# Power_Components.net
KiCad netlist of a schematic drawn in Altium Designer
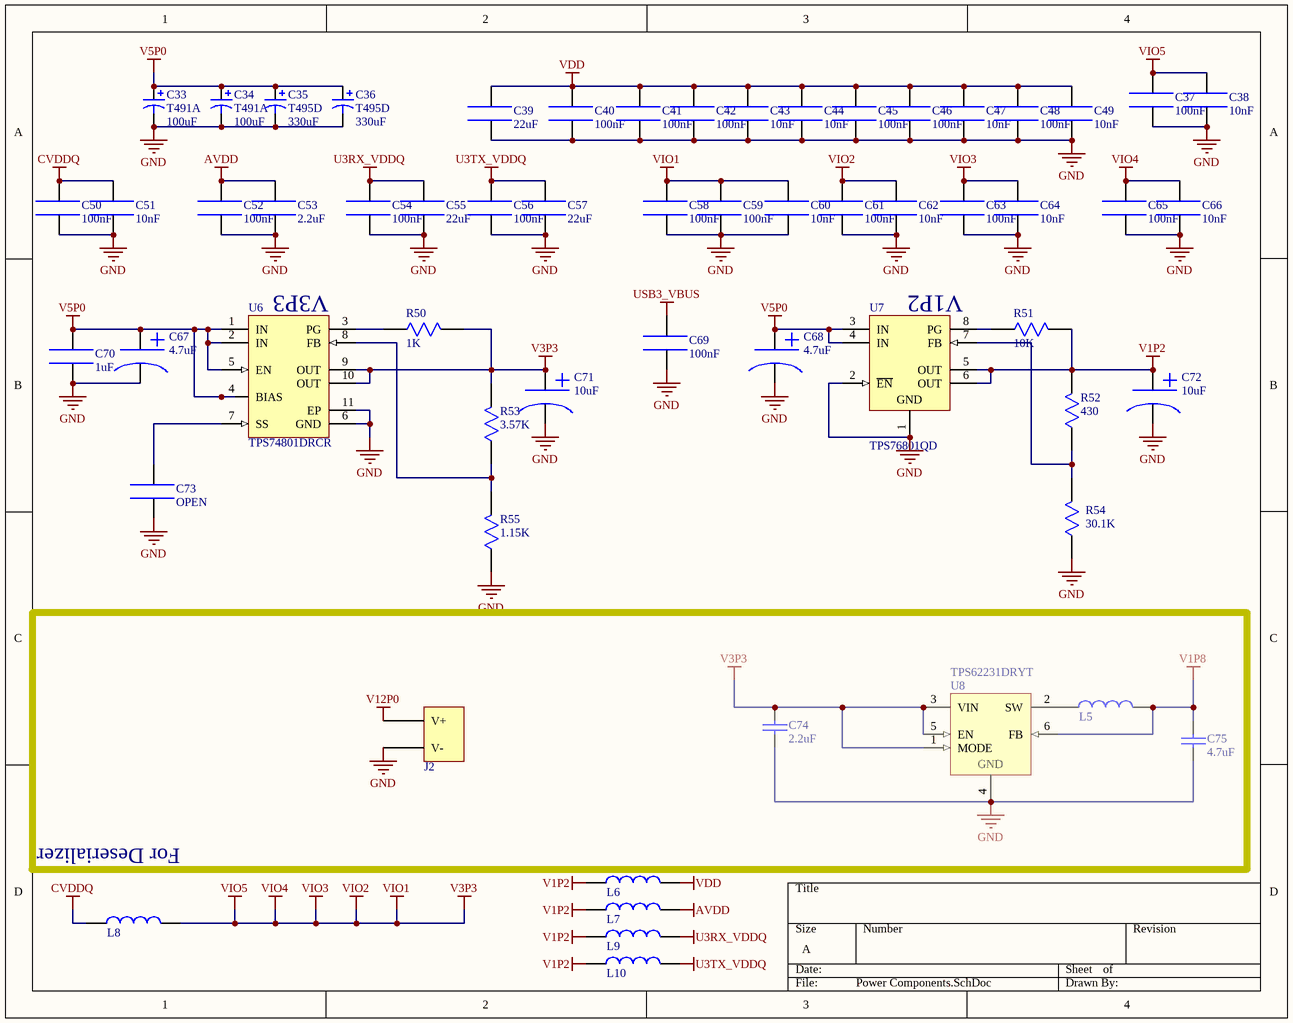
[diagram p0: Power Components.SchDoc]

(export (version "E")
  (design (tool "Eeschema 10.0.6"))
  (components
    (comp (ref "C33")
      (value "T491A")
      (footprint "A")
      (description "Solid Tantalum Chip Capacitor, Standard T491 Series - Industrial Grade")
      (fields (field (name "ALTIUM_VALUE") "100uF") (field (name "PUBLISHER") "Altium Limited"))
      (libsource (lib "KEMET Chip Capacitor") (part "T491A"))
    )
    (comp (ref "C34")
      (value "T491A")
      (footprint "A")
      (description "Solid Tantalum Chip Capacitor, Standard T491 Series - Industrial Grade")
      (fields (field (name "ALTIUM_VALUE") "100uF") (field (name "PUBLISHER") "Altium Limited"))
      (libsource (lib "KEMET Chip Capacitor") (part "T491A"))
    )
    (comp (ref "C35")
      (value "T495D")
      (footprint "D")
      (description "Solid Tantalum Chip Capacitor, Standard T495 Series - Low ESR, Surge Robust")
      (fields (field (name "ALTIUM_VALUE") "330uF") (field (name "PUBLISHER") "Altium Limited"))
      (libsource (lib "KEMET Chip Capacitor") (part "T495D"))
    )
    (comp (ref "C36")
      (value "T495D")
      (footprint "D")
      (description "Solid Tantalum Chip Capacitor, Standard T495 Series - Low ESR, Surge Robust")
      (fields (field (name "ALTIUM_VALUE") "330uF") (field (name "PUBLISHER") "Altium Limited"))
      (libsource (lib "KEMET Chip Capacitor") (part "T495D"))
    )
    (comp (ref "C37")
      (value "100nF")
      (footprint "SMD Capacitor 0603")
      (fields (field (name "Comment") "Capacitor"))
      (libsource (lib "DA_Component_Library") (part "Capacitor"))
    )
    (comp (ref "C38")
      (value "10nF")
      (footprint "SMD Capacitor 0603")
      (fields (field (name "Comment") "Capacitor"))
      (libsource (lib "DA_Component_Library") (part "Capacitor"))
    )
    (comp (ref "C39")
      (value "22uF")
      (footprint "SMD Capacitor 0603")
      (fields (field (name "Comment") "Capacitor"))
      (libsource (lib "DA_Component_Library") (part "Capacitor"))
    )
    (comp (ref "C40")
      (value "100nF")
      (footprint "SMD Capacitor 0603")
      (fields (field (name "Comment") "Capacitor"))
      (libsource (lib "DA_Component_Library") (part "Capacitor"))
    )
    (comp (ref "C41")
      (value "100nF")
      (footprint "SMD Capacitor 0603")
      (fields (field (name "Comment") "Capacitor"))
      (libsource (lib "DA_Component_Library") (part "Capacitor"))
    )
    (comp (ref "C42")
      (value "100nF")
      (footprint "SMD Capacitor 0603")
      (fields (field (name "Comment") "Capacitor"))
      (libsource (lib "DA_Component_Library") (part "Capacitor"))
    )
    (comp (ref "C43")
      (value "10nF")
      (footprint "SMD Capacitor 0603")
      (fields (field (name "Comment") "Capacitor"))
      (libsource (lib "DA_Component_Library") (part "Capacitor"))
    )
    (comp (ref "C44")
      (value "10nF")
      (footprint "SMD Capacitor 0603")
      (fields (field (name "Comment") "Capacitor"))
      (libsource (lib "DA_Component_Library") (part "Capacitor"))
    )
    (comp (ref "C45")
      (value "100nF")
      (footprint "SMD Capacitor 0603")
      (fields (field (name "Comment") "Capacitor"))
      (libsource (lib "DA_Component_Library") (part "Capacitor"))
    )
    (comp (ref "C46")
      (value "100nF")
      (footprint "SMD Capacitor 0603")
      (fields (field (name "Comment") "Capacitor"))
      (libsource (lib "DA_Component_Library") (part "Capacitor"))
    )
    (comp (ref "C47")
      (value "10nF")
      (footprint "SMD Capacitor 0603")
      (fields (field (name "Comment") "Capacitor"))
      (libsource (lib "DA_Component_Library") (part "Capacitor"))
    )
    (comp (ref "C48")
      (value "100nF")
      (footprint "SMD Capacitor 0603")
      (fields (field (name "Comment") "Capacitor"))
      (libsource (lib "DA_Component_Library") (part "Capacitor"))
    )
    (comp (ref "C49")
      (value "10nF")
      (footprint "SMD Capacitor 0603")
      (fields (field (name "Comment") "Capacitor"))
      (libsource (lib "DA_Component_Library") (part "Capacitor"))
    )
    (comp (ref "C50")
      (value "100nF")
      (footprint "SMD Capacitor 0603")
      (fields (field (name "Comment") "Capacitor"))
      (libsource (lib "DA_Component_Library") (part "Capacitor"))
    )
    (comp (ref "C51")
      (value "10nF")
      (footprint "SMD Capacitor 0603")
      (fields (field (name "Comment") "Capacitor"))
      (libsource (lib "DA_Component_Library") (part "Capacitor"))
    )
    (comp (ref "C52")
      (value "100nF")
      (footprint "SMD Capacitor 0603")
      (fields (field (name "Comment") "Capacitor"))
      (libsource (lib "DA_Component_Library") (part "Capacitor"))
    )
    (comp (ref "C53")
      (value "2.2uF")
      (footprint "SMD Capacitor 0603")
      (fields (field (name "Comment") "Capacitor"))
      (libsource (lib "DA_Component_Library") (part "Capacitor"))
    )
    (comp (ref "C54")
      (value "100nF")
      (footprint "SMD Capacitor 0603")
      (fields (field (name "Comment") "Capacitor"))
      (libsource (lib "DA_Component_Library") (part "Capacitor"))
    )
    (comp (ref "C55")
      (value "22uF")
      (footprint "SMD Capacitor 0603")
      (fields (field (name "Comment") "Capacitor"))
      (libsource (lib "DA_Component_Library") (part "Capacitor"))
    )
    (comp (ref "C56")
      (value "100nF")
      (footprint "SMD Capacitor 0603")
      (fields (field (name "Comment") "Capacitor"))
      (libsource (lib "DA_Component_Library") (part "Capacitor"))
    )
    (comp (ref "C57")
      (value "22uF")
      (footprint "SMD Capacitor 0603")
      (fields (field (name "Comment") "Capacitor"))
      (libsource (lib "DA_Component_Library") (part "Capacitor"))
    )
    (comp (ref "C58")
      (value "100nF")
      (footprint "SMD Capacitor 0603")
      (fields (field (name "Comment") "Capacitor"))
      (libsource (lib "DA_Component_Library") (part "Capacitor"))
    )
    (comp (ref "C59")
      (value "100nF")
      (footprint "SMD Capacitor 0603")
      (fields (field (name "Comment") "Capacitor"))
      (libsource (lib "DA_Component_Library") (part "Capacitor"))
    )
    (comp (ref "C60")
      (value "10nF")
      (footprint "SMD Capacitor 0603")
      (fields (field (name "Comment") "Capacitor"))
      (libsource (lib "DA_Component_Library") (part "Capacitor"))
    )
    (comp (ref "C61")
      (value "100nF")
      (footprint "SMD Capacitor 0603")
      (fields (field (name "Comment") "Capacitor"))
      (libsource (lib "DA_Component_Library") (part "Capacitor"))
    )
    (comp (ref "C62")
      (value "10nF")
      (footprint "SMD Capacitor 0603")
      (fields (field (name "Comment") "Capacitor"))
      (libsource (lib "DA_Component_Library") (part "Capacitor"))
    )
    (comp (ref "C63")
      (value "100nF")
      (footprint "SMD Capacitor 0603")
      (fields (field (name "Comment") "Capacitor"))
      (libsource (lib "DA_Component_Library") (part "Capacitor"))
    )
    (comp (ref "C64")
      (value "10nF")
      (footprint "SMD Capacitor 0603")
      (fields (field (name "Comment") "Capacitor"))
      (libsource (lib "DA_Component_Library") (part "Capacitor"))
    )
    (comp (ref "C65")
      (value "100nF")
      (footprint "SMD Capacitor 0603")
      (fields (field (name "Comment") "Capacitor"))
      (libsource (lib "DA_Component_Library") (part "Capacitor"))
    )
    (comp (ref "C66")
      (value "10nF")
      (footprint "SMD Capacitor 0603")
      (fields (field (name "Comment") "Capacitor"))
      (libsource (lib "DA_Component_Library") (part "Capacitor"))
    )
    (comp (ref "C67")
      (value "4.7uF")
      (footprint "Capacitor Polarized 0603")
      (fields (field (name "Comment") "Capacitor Polarized"))
      (libsource (lib "DA_Component_Library") (part "Capacitor Polarized"))
    )
    (comp (ref "C68")
      (value "4.7uF")
      (footprint "Capacitor Polarized 0603")
      (fields (field (name "Comment") "Capacitor Polarized"))
      (libsource (lib "DA_Component_Library") (part "Capacitor Polarized"))
    )
    (comp (ref "C69")
      (value "100nF")
      (footprint "SMD Capacitor 0603")
      (fields (field (name "Comment") "Capacitor"))
      (libsource (lib "DA_Component_Library") (part "Capacitor"))
    )
    (comp (ref "C70")
      (value "1uF")
      (footprint "SMD Capacitor 0603")
      (fields (field (name "Comment") "Capacitor"))
      (libsource (lib "DA_Component_Library") (part "Capacitor"))
    )
    (comp (ref "C71")
      (value "10uF")
      (footprint "Capacitor Polarized 0603")
      (fields (field (name "Comment") "Capacitor Polarized"))
      (libsource (lib "DA_Component_Library") (part "Capacitor Polarized"))
    )
    (comp (ref "C72")
      (value "10uF")
      (footprint "Capacitor Polarized 0603")
      (fields (field (name "Comment") "Capacitor Polarized"))
      (libsource (lib "DA_Component_Library") (part "Capacitor Polarized"))
    )
    (comp (ref "C73")
      (value "OPEN")
      (footprint "SMD Capacitor 0603")
      (fields (field (name "Comment") "Capacitor"))
      (libsource (lib "DA_Component_Library") (part "Capacitor"))
    )
    (comp (ref "C74")
      (value "2.2uF")
      (footprint "SMD Capacitor 0603")
      (libsource (lib "") (part "Capacitor_1"))
    )
    (comp (ref "C75")
      (value "4.7uF")
      (footprint "SMD Capacitor 0603")
      (libsource (lib "") (part "Capacitor_1"))
    )
    (comp (ref "J2")
      (value "DC-Power Jack")
      (footprint "PCBComponent_1 - duplicate")
      (libsource (lib "DA_Component_Library") (part "DC-Power Jack"))
    )
    (comp (ref "L5")
      (value "Ferrite Bead")
      (footprint "LQM21PN2R2MC0D")
      (libsource (lib "DA_Component_Library") (part "Ferrite Bead"))
    )
    (comp (ref "L6")
      (value "Ferrite Bead")
      (footprint "MPZ2012S601A")
      (libsource (lib "DA_Component_Library") (part "Ferrite Bead"))
    )
    (comp (ref "L7")
      (value "Ferrite Bead")
      (footprint "MPZ2012S601A")
      (libsource (lib "DA_Component_Library") (part "Ferrite Bead"))
    )
    (comp (ref "L8")
      (value "Ferrite Bead")
      (footprint "MPZ2012S601A")
      (libsource (lib "DA_Component_Library") (part "Ferrite Bead"))
    )
    (comp (ref "L9")
      (value "Ferrite Bead")
      (footprint "MPZ2012S601A")
      (libsource (lib "DA_Component_Library") (part "Ferrite Bead"))
    )
    (comp (ref "L10")
      (value "Ferrite Bead")
      (footprint "MPZ2012S601A")
      (libsource (lib "DA_Component_Library") (part "Ferrite Bead"))
    )
    (comp (ref "R50")
      (value "1K")
      (footprint "SMD Resistor 0603")
      (fields (field (name "Comment") "Resistor"))
      (libsource (lib "DA_Component_Library") (part "Resistor"))
    )
    (comp (ref "R51")
      (value "10K")
      (footprint "SMD Resistor 0603")
      (fields (field (name "Comment") "Resistor"))
      (libsource (lib "DA_Component_Library") (part "Resistor"))
    )
    (comp (ref "R52")
      (value "430")
      (footprint "SMD Resistor 0603")
      (fields (field (name "Comment") "Resistor"))
      (libsource (lib "DA_Component_Library") (part "Resistor"))
    )
    (comp (ref "R53")
      (value "3.57K")
      (footprint "SMD Resistor 0603")
      (fields (field (name "Comment") "Resistor"))
      (libsource (lib "DA_Component_Library") (part "Resistor"))
    )
    (comp (ref "R54")
      (value "30.1K")
      (footprint "SMD Resistor 0603")
      (fields (field (name "Comment") "Resistor"))
      (libsource (lib "DA_Component_Library") (part "Resistor"))
    )
    (comp (ref "R55")
      (value "1.15K")
      (footprint "SMD Resistor 0603")
      (fields (field (name "Comment") "Resistor"))
      (libsource (lib "DA_Component_Library") (part "Resistor"))
    )
    (comp (ref "U6")
      (value "TPS74801DRCR")
      (footprint "TI-DRC10-2400X1650TP_V")
      (fields (field (name "MANUFACTURER") "Texas Instruments"))
      (libsource (lib "TI Power Management Linear Regulator Single Channel LDO (400-7500mA)") (part "TPS74801DRCR"))
    )
    (comp (ref "U7")
      (value "TPS76801QD")
      (footprint "TI-D8_N")
      (fields (field (name "MANUFACTURER") "Texas Instruments"))
      (libsource (lib "TI Power Management Linear Regulator Single Channel LDO (400-7500mA)") (part "TPS76801QD"))
    )
    (comp (ref "U8")
      (value "TPS62231DRYT")
      (footprint "DRY6")
      (fields (field (name "MANUFACTURER") "Texas Instruments"))
      (libsource (lib "TI Power Management Step-Down Regulator") (part "TPS62231DRYT"))
    )
  )
  (nets
    (net (code "1") (name "AVDD") (class "Default")
      (node (ref "C52") (pin "1") (pinfunction "1_1") (pintype "passive"))
      (node (ref "C53") (pin "1") (pinfunction "1_1") (pintype "passive"))
      (node (ref "L7") (pin "2") (pinfunction "2_2") (pintype "passive"))
    )
    (net (code "2") (name "CVDDQ") (class "Default")
      (node (ref "C50") (pin "1") (pinfunction "1_1") (pintype "passive"))
      (node (ref "C51") (pin "1") (pinfunction "1_1") (pintype "passive"))
      (node (ref "L8") (pin "1") (pinfunction "1_1") (pintype "passive"))
    )
    (net (code "3") (name "GND") (class "Default")
      (node (ref "C33") (pin "2") (pinfunction "2_2") (pintype "passive"))
      (node (ref "C34") (pin "2") (pinfunction "2_2") (pintype "passive"))
      (node (ref "C35") (pin "2") (pinfunction "2_2") (pintype "passive"))
      (node (ref "C36") (pin "2") (pinfunction "2_2") (pintype "passive"))
      (node (ref "C37") (pin "0") (pinfunction "0_0") (pintype "passive"))
      (node (ref "C38") (pin "0") (pinfunction "0_0") (pintype "passive"))
      (node (ref "C39") (pin "0") (pinfunction "0_0") (pintype "passive"))
      (node (ref "C40") (pin "0") (pinfunction "0_0") (pintype "passive"))
      (node (ref "C41") (pin "0") (pinfunction "0_0") (pintype "passive"))
      (node (ref "C42") (pin "0") (pinfunction "0_0") (pintype "passive"))
      (node (ref "C43") (pin "0") (pinfunction "0_0") (pintype "passive"))
      (node (ref "C44") (pin "0") (pinfunction "0_0") (pintype "passive"))
      (node (ref "C45") (pin "0") (pinfunction "0_0") (pintype "passive"))
      (node (ref "C46") (pin "0") (pinfunction "0_0") (pintype "passive"))
      (node (ref "C47") (pin "0") (pinfunction "0_0") (pintype "passive"))
      (node (ref "C48") (pin "0") (pinfunction "0_0") (pintype "passive"))
      (node (ref "C49") (pin "0") (pinfunction "0_0") (pintype "passive"))
      (node (ref "C50") (pin "0") (pinfunction "0_0") (pintype "passive"))
      (node (ref "C51") (pin "0") (pinfunction "0_0") (pintype "passive"))
      (node (ref "C52") (pin "0") (pinfunction "0_0") (pintype "passive"))
      (node (ref "C53") (pin "0") (pinfunction "0_0") (pintype "passive"))
      (node (ref "C54") (pin "0") (pinfunction "0_0") (pintype "passive"))
      (node (ref "C55") (pin "0") (pinfunction "0_0") (pintype "passive"))
      (node (ref "C56") (pin "0") (pinfunction "0_0") (pintype "passive"))
      (node (ref "C57") (pin "0") (pinfunction "0_0") (pintype "passive"))
      (node (ref "C58") (pin "0") (pinfunction "0_0") (pintype "passive"))
      (node (ref "C59") (pin "0") (pinfunction "0_0") (pintype "passive"))
      (node (ref "C60") (pin "0") (pinfunction "0_0") (pintype "passive"))
      (node (ref "C61") (pin "0") (pinfunction "0_0") (pintype "passive"))
      (node (ref "C62") (pin "0") (pinfunction "0_0") (pintype "passive"))
      (node (ref "C63") (pin "0") (pinfunction "0_0") (pintype "passive"))
      (node (ref "C64") (pin "0") (pinfunction "0_0") (pintype "passive"))
      (node (ref "C65") (pin "0") (pinfunction "0_0") (pintype "passive"))
      (node (ref "C66") (pin "0") (pinfunction "0_0") (pintype "passive"))
      (node (ref "C67") (pin "-") (pinfunction "-_-") (pintype "passive"))
      (node (ref "C68") (pin "-") (pinfunction "-_-") (pintype "passive"))
      (node (ref "C69") (pin "0") (pinfunction "0_0") (pintype "passive"))
      (node (ref "C70") (pin "0") (pinfunction "0_0") (pintype "passive"))
      (node (ref "C71") (pin "-") (pinfunction "-_-") (pintype "passive"))
      (node (ref "C72") (pin "-") (pinfunction "-_-") (pintype "passive"))
      (node (ref "C73") (pin "0") (pinfunction "0_0") (pintype "passive"))
      (node (ref "C74") (pin "1") (pinfunction "1_1") (pintype "passive"))
      (node (ref "C75") (pin "1") (pinfunction "1_1") (pintype "passive"))
      (node (ref "J2") (pin "V-") (pinfunction "V-_V-") (pintype "passive"))
      (node (ref "R54") (pin "0") (pinfunction "0_0") (pintype "passive"))
      (node (ref "R55") (pin "0") (pinfunction "0_0") (pintype "passive"))
      (node (ref "U6") (pin "11") (pinfunction "EP_11") (pintype "power_in"))
      (node (ref "U6") (pin "6") (pinfunction "GND_6") (pintype "power_in"))
      (node (ref "U7") (pin "1") (pinfunction "GND_1") (pintype "power_in"))
      (node (ref "U7") (pin "2") (pinfunction "~{EN}_2") (pintype "input"))
      (node (ref "U8") (pin "4") (pinfunction "GND_4") (pintype "power_in"))
    )
    (net (code "4") (name "Net-(U6-FB)") (class "Default")
      (node (ref "R53") (pin "0") (pinfunction "0_0") (pintype "passive"))
      (node (ref "R55") (pin "1") (pinfunction "1_1") (pintype "passive"))
      (node (ref "U6") (pin "8") (pinfunction "FB_8") (pintype "input"))
    )
    (net (code "5") (name "Net-(U6-PG)") (class "Default")
      (node (ref "R50") (pin "0") (pinfunction "0_0") (pintype "passive"))
      (node (ref "U6") (pin "3") (pinfunction "PG_3") (pintype "tri_state"))
    )
    (net (code "6") (name "Net-(U6-SS)") (class "Default")
      (node (ref "C73") (pin "1") (pinfunction "1_1") (pintype "passive"))
      (node (ref "U6") (pin "7") (pinfunction "SS_7") (pintype "input"))
    )
    (net (code "7") (name "Net-(U7-FB)") (class "Default")
      (node (ref "R52") (pin "0") (pinfunction "0_0") (pintype "passive"))
      (node (ref "R54") (pin "1") (pinfunction "1_1") (pintype "passive"))
      (node (ref "U7") (pin "7") (pinfunction "FB_7") (pintype "input"))
    )
    (net (code "8") (name "Net-(U7-PG)") (class "Default")
      (node (ref "R51") (pin "0") (pinfunction "0_0") (pintype "passive"))
      (node (ref "U7") (pin "8") (pinfunction "PG_8") (pintype "tri_state"))
    )
    (net (code "9") (name "Net-(U8-SW)") (class "Default")
      (node (ref "L5") (pin "1") (pinfunction "1_1") (pintype "passive"))
      (node (ref "U8") (pin "2") (pinfunction "SW_2") (pintype "power_in"))
    )
    (net (code "10") (name "U3RX_VDDQ") (class "Default")
      (node (ref "C54") (pin "1") (pinfunction "1_1") (pintype "passive"))
      (node (ref "C55") (pin "1") (pinfunction "1_1") (pintype "passive"))
      (node (ref "L9") (pin "2") (pinfunction "2_2") (pintype "passive"))
    )
    (net (code "11") (name "U3TX_VDDQ") (class "Default")
      (node (ref "C56") (pin "1") (pinfunction "1_1") (pintype "passive"))
      (node (ref "C57") (pin "1") (pinfunction "1_1") (pintype "passive"))
      (node (ref "L10") (pin "2") (pinfunction "2_2") (pintype "passive"))
    )
    (net (code "12") (name "USB3_VBUS") (class "Default")
      (node (ref "C69") (pin "1") (pinfunction "1_1") (pintype "passive"))
    )
    (net (code "13") (name "V1P2") (class "Default")
      (node (ref "C72") (pin "+") (pinfunction "+_+") (pintype "passive"))
      (node (ref "L10") (pin "1") (pinfunction "1_1") (pintype "passive"))
      (node (ref "L6") (pin "1") (pinfunction "1_1") (pintype "passive"))
      (node (ref "L7") (pin "1") (pinfunction "1_1") (pintype "passive"))
      (node (ref "L9") (pin "1") (pinfunction "1_1") (pintype "passive"))
      (node (ref "R51") (pin "1") (pinfunction "1_1") (pintype "passive"))
      (node (ref "R52") (pin "1") (pinfunction "1_1") (pintype "passive"))
      (node (ref "U7") (pin "5") (pinfunction "OUT_5") (pintype "power_in"))
      (node (ref "U7") (pin "6") (pinfunction "OUT_6") (pintype "power_in"))
    )
    (net (code "14") (name "V1P8") (class "Default")
      (node (ref "C75") (pin "0") (pinfunction "0_0") (pintype "passive"))
      (node (ref "L5") (pin "2") (pinfunction "2_2") (pintype "passive"))
      (node (ref "U8") (pin "6") (pinfunction "FB_6") (pintype "input"))
    )
    (net (code "15") (name "V3P3") (class "Default")
      (node (ref "C37") (pin "1") (pinfunction "1_1") (pintype "passive"))
      (node (ref "C38") (pin "1") (pinfunction "1_1") (pintype "passive"))
      (node (ref "C58") (pin "1") (pinfunction "1_1") (pintype "passive"))
      (node (ref "C59") (pin "1") (pinfunction "1_1") (pintype "passive"))
      (node (ref "C60") (pin "1") (pinfunction "1_1") (pintype "passive"))
      (node (ref "C61") (pin "1") (pinfunction "1_1") (pintype "passive"))
      (node (ref "C62") (pin "1") (pinfunction "1_1") (pintype "passive"))
      (node (ref "C63") (pin "1") (pinfunction "1_1") (pintype "passive"))
      (node (ref "C64") (pin "1") (pinfunction "1_1") (pintype "passive"))
      (node (ref "C65") (pin "1") (pinfunction "1_1") (pintype "passive"))
      (node (ref "C66") (pin "1") (pinfunction "1_1") (pintype "passive"))
      (node (ref "C71") (pin "+") (pinfunction "+_+") (pintype "passive"))
      (node (ref "C74") (pin "0") (pinfunction "0_0") (pintype "passive"))
      (node (ref "L8") (pin "2") (pinfunction "2_2") (pintype "passive"))
      (node (ref "R50") (pin "1") (pinfunction "1_1") (pintype "passive"))
      (node (ref "R53") (pin "1") (pinfunction "1_1") (pintype "passive"))
      (node (ref "U6") (pin "10") (pinfunction "OUT_10") (pintype "power_in"))
      (node (ref "U6") (pin "9") (pinfunction "OUT_9") (pintype "power_in"))
      (node (ref "U8") (pin "1") (pinfunction "MODE_1") (pintype "input"))
      (node (ref "U8") (pin "3") (pinfunction "VIN_3") (pintype "power_in"))
      (node (ref "U8") (pin "5") (pinfunction "EN_5") (pintype "input"))
    )
    (net (code "16") (name "V5P0") (class "Default")
      (node (ref "C33") (pin "1") (pinfunction "1_1") (pintype "passive"))
      (node (ref "C34") (pin "1") (pinfunction "1_1") (pintype "passive"))
      (node (ref "C35") (pin "1") (pinfunction "1_1") (pintype "passive"))
      (node (ref "C36") (pin "1") (pinfunction "1_1") (pintype "passive"))
      (node (ref "C67") (pin "+") (pinfunction "+_+") (pintype "passive"))
      (node (ref "C68") (pin "+") (pinfunction "+_+") (pintype "passive"))
      (node (ref "C70") (pin "1") (pinfunction "1_1") (pintype "passive"))
      (node (ref "U6") (pin "1") (pinfunction "IN_1") (pintype "power_in"))
      (node (ref "U6") (pin "2") (pinfunction "IN_2") (pintype "power_in"))
      (node (ref "U6") (pin "4") (pinfunction "BIAS_4") (pintype "power_in"))
      (node (ref "U6") (pin "5") (pinfunction "EN_5") (pintype "input"))
      (node (ref "U7") (pin "3") (pinfunction "IN_3") (pintype "power_in"))
      (node (ref "U7") (pin "4") (pinfunction "IN_4") (pintype "power_in"))
    )
    (net (code "17") (name "V12P0") (class "Default")
      (node (ref "J2") (pin "V+") (pinfunction "V+_V+") (pintype "passive"))
    )
    (net (code "18") (name "VDD") (class "Default")
      (node (ref "C39") (pin "1") (pinfunction "1_1") (pintype "passive"))
      (node (ref "C40") (pin "1") (pinfunction "1_1") (pintype "passive"))
      (node (ref "C41") (pin "1") (pinfunction "1_1") (pintype "passive"))
      (node (ref "C42") (pin "1") (pinfunction "1_1") (pintype "passive"))
      (node (ref "C43") (pin "1") (pinfunction "1_1") (pintype "passive"))
      (node (ref "C44") (pin "1") (pinfunction "1_1") (pintype "passive"))
      (node (ref "C45") (pin "1") (pinfunction "1_1") (pintype "passive"))
      (node (ref "C46") (pin "1") (pinfunction "1_1") (pintype "passive"))
      (node (ref "C47") (pin "1") (pinfunction "1_1") (pintype "passive"))
      (node (ref "C48") (pin "1") (pinfunction "1_1") (pintype "passive"))
      (node (ref "C49") (pin "1") (pinfunction "1_1") (pintype "passive"))
      (node (ref "L6") (pin "2") (pinfunction "2_2") (pintype "passive"))
    )
  )
)
